# 02_power_mppc.net
KiCad netlist of a schematic drawn in Altium Designer
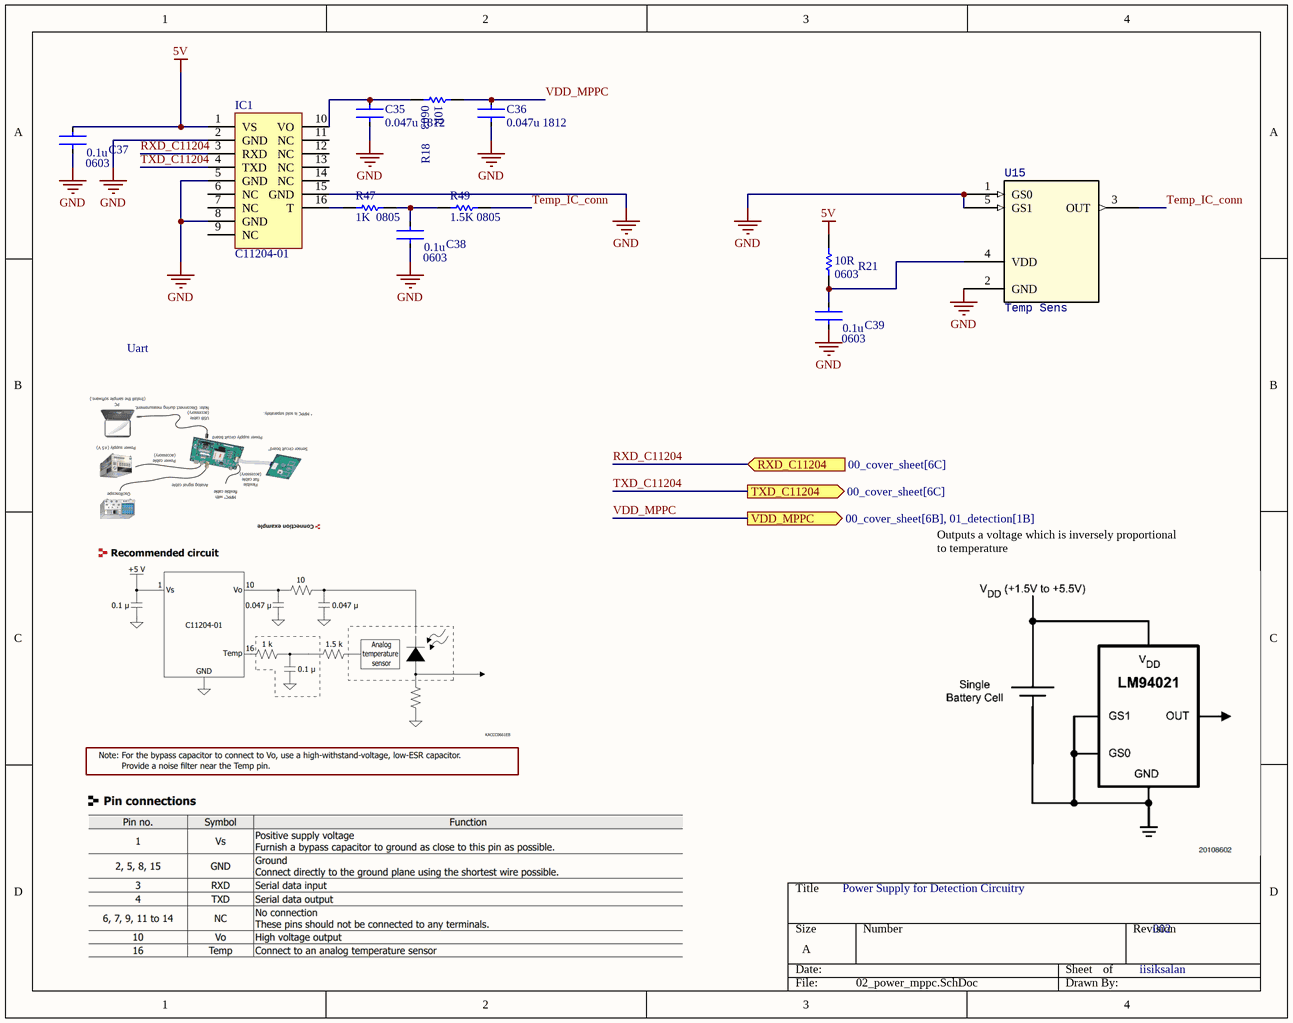
[diagram p0: 02_power_mppc.SchDoc]

(export (version "E")
  (design (tool "Eeschema 10.0.6"))
  (components
    (comp (ref "C35")
      (value "0.047u 1812")
      (footprint "1812")
      (description "CAP CER 0.047UF 100V C0GNP0 1812")
      (libsource (lib "tcspc00") (part "C1812C473F1GAC7800"))
    )
    (comp (ref "C36")
      (value "0.047u 1812")
      (footprint "1812")
      (description "CAP CER 0.047UF 100V C0GNP0 1812")
      (libsource (lib "tcspc00") (part "C1812C473F1GAC7800"))
    )
    (comp (ref "C37")
      (value "CGA3E2X7R1H104K080AA")
      (footprint "CAPTDK0603")
      (description "CAP CER 0.1UF 50V X7R 0603")
      (libsource (lib "tcspc00") (part "CGA3E2X7R1H104K080AA"))
    )
    (comp (ref "C38")
      (value "CGA3E2X7R1H104K080AA")
      (footprint "CAPTDK0603")
      (description "CAP CER 0.1UF 50V X7R 0603")
      (libsource (lib "tcspc00") (part "CGA3E2X7R1H104K080AA"))
    )
    (comp (ref "C39")
      (value "CGA3E2X7R1H104K080AA")
      (footprint "CAPTDK0603")
      (description "CAP CER 0.1UF 50V X7R 0603")
      (libsource (lib "tcspc00") (part "CGA3E2X7R1H104K080AA"))
    )
    (comp (ref "IC1")
      (value "C11204-01")
      (footprint "MPPC_POWER_C11204-01")
      (description "MPPC Hamamutsa Power IC")
      (libsource (lib "tcspc00") (part "MPPC-Power"))
    )
    (comp (ref "R18")
      (value "RMCF0603FT10R0")
      (footprint "RES-STACK-POLE-0603")
      (description "RES 10 OHM 1% 1/10W 0603")
      (libsource (lib "tcspc00") (part "RMCF0603FT10R0"))
    )
    (comp (ref "R21")
      (value "RMCF0603FT10R0")
      (footprint "RES-STACK-POLE-0603")
      (description "RES 10 OHM 1% 1/10W 0603")
      (libsource (lib "tcspc00") (part "RMCF0603FT10R0"))
    )
    (comp (ref "R47")
      (value "1K  0805")
      (footprint "RES-STACK-POLE-0805")
      (description "RES 1K OHM 1% 1/4W 0805")
      (libsource (lib "tcspc00") (part "RK73H2ATTD1001F"))
    )
    (comp (ref "R49")
      (value "1.5K 0805")
      (footprint "RES-STACK-POLE-0805")
      (description "RES 1.5K OHM 1% 1/4W 0805")
      (libsource (lib "tcspc00") (part "RK73H2ATTD1501F"))
    )
    (comp (ref "U15")
      (value "Temp Sens")
      (footprint "SOT-1.1")
      (description "SENSOR ANALOG -50C-150C SC70-5")
      (libsource (lib "tcspc00") (part "LM94021BIMGX/NOPB"))
    )
  )
  (nets
    (net (code "1") (name "/RXD_C11204") (class "Default")
      (node (ref "IC1") (pin "3") (pinfunction "RXD_3") (pintype "passive"))
    )
    (net (code "2") (name "/TXD_C11204") (class "Default")
      (node (ref "IC1") (pin "4") (pinfunction "TXD_4") (pintype "passive"))
    )
    (net (code "3") (name "/Temp_IC_conn") (class "Default")
      (node (ref "R49") (pin "2") (pinfunction "2_2") (pintype "passive"))
      (node (ref "U15") (pin "3") (pinfunction "OUT_3") (pintype "output"))
    )
    (net (code "4") (name "/VDD_MPPC") (class "Default")
      (node (ref "C36") (pin "1") (pinfunction "1_1") (pintype "passive"))
      (node (ref "R18") (pin "2") (pinfunction "2_2") (pintype "passive"))
    )
    (net (code "5") (name "5V") (class "Default")
      (node (ref "C37") (pin "1") (pinfunction "1_1") (pintype "passive"))
      (node (ref "IC1") (pin "1") (pinfunction "VS_1") (pintype "passive"))
      (node (ref "R21") (pin "2") (pinfunction "2_2") (pintype "passive"))
    )
    (net (code "6") (name "GND") (class "Default")
      (node (ref "C35") (pin "2") (pinfunction "2_2") (pintype "passive"))
      (node (ref "C36") (pin "2") (pinfunction "2_2") (pintype "passive"))
      (node (ref "C37") (pin "2") (pinfunction "2_2") (pintype "passive"))
      (node (ref "C38") (pin "2") (pinfunction "2_2") (pintype "passive"))
      (node (ref "C39") (pin "2") (pinfunction "2_2") (pintype "passive"))
      (node (ref "IC1") (pin "15") (pinfunction "GND_15") (pintype "passive"))
      (node (ref "IC1") (pin "2") (pinfunction "GND_2") (pintype "passive"))
      (node (ref "IC1") (pin "5") (pinfunction "GND_5") (pintype "passive"))
      (node (ref "IC1") (pin "8") (pinfunction "GND_8") (pintype "passive"))
      (node (ref "U15") (pin "1") (pinfunction "GS0_1") (pintype "input"))
      (node (ref "U15") (pin "2") (pinfunction "GND_2") (pintype "power_in"))
      (node (ref "U15") (pin "5") (pinfunction "GS1_5") (pintype "input"))
    )
    (net (code "7") (name "Net-(C38-Pad1)") (class "Default")
      (node (ref "C38") (pin "1") (pinfunction "1_1") (pintype "passive"))
      (node (ref "R47") (pin "2") (pinfunction "2_2") (pintype "passive"))
      (node (ref "R49") (pin "1") (pinfunction "1_1") (pintype "passive"))
    )
    (net (code "8") (name "Net-(IC1-T)") (class "Default")
      (node (ref "IC1") (pin "16") (pinfunction "T_16") (pintype "passive"))
      (node (ref "R47") (pin "1") (pinfunction "1_1") (pintype "passive"))
    )
    (net (code "9") (name "Net-(IC1-VO)") (class "Default")
      (node (ref "C35") (pin "1") (pinfunction "1_1") (pintype "passive"))
      (node (ref "IC1") (pin "10") (pinfunction "VO_10") (pintype "passive"))
      (node (ref "R18") (pin "1") (pinfunction "1_1") (pintype "passive"))
    )
    (net (code "10") (name "Net-(U15-VDD)") (class "Default")
      (node (ref "C39") (pin "1") (pinfunction "1_1") (pintype "passive"))
      (node (ref "R21") (pin "1") (pinfunction "1_1") (pintype "passive"))
      (node (ref "U15") (pin "4") (pinfunction "VDD_4") (pintype "power_in"))
    )
    (net (code "11") (name "unconnected-(IC1-NC-Pad6)") (class "Default")
      (node (ref "IC1") (pin "6") (pinfunction "NC_6") (pintype "passive"))
    )
    (net (code "12") (name "unconnected-(IC1-NC-Pad7)") (class "Default")
      (node (ref "IC1") (pin "7") (pinfunction "NC_7") (pintype "passive"))
    )
    (net (code "13") (name "unconnected-(IC1-NC-Pad9)") (class "Default")
      (node (ref "IC1") (pin "9") (pinfunction "NC_9") (pintype "passive"))
    )
    (net (code "14") (name "unconnected-(IC1-NC-Pad11)") (class "Default")
      (node (ref "IC1") (pin "11") (pinfunction "NC_11") (pintype "passive"))
    )
    (net (code "15") (name "unconnected-(IC1-NC-Pad12)") (class "Default")
      (node (ref "IC1") (pin "12") (pinfunction "NC_12") (pintype "passive"))
    )
    (net (code "16") (name "unconnected-(IC1-NC-Pad13)") (class "Default")
      (node (ref "IC1") (pin "13") (pinfunction "NC_13") (pintype "passive"))
    )
    (net (code "17") (name "unconnected-(IC1-NC-Pad14)") (class "Default")
      (node (ref "IC1") (pin "14") (pinfunction "NC_14") (pintype "passive"))
    )
  )
)
